# 10_i2c.net
KiCad netlist of a schematic drawn in Altium Designer
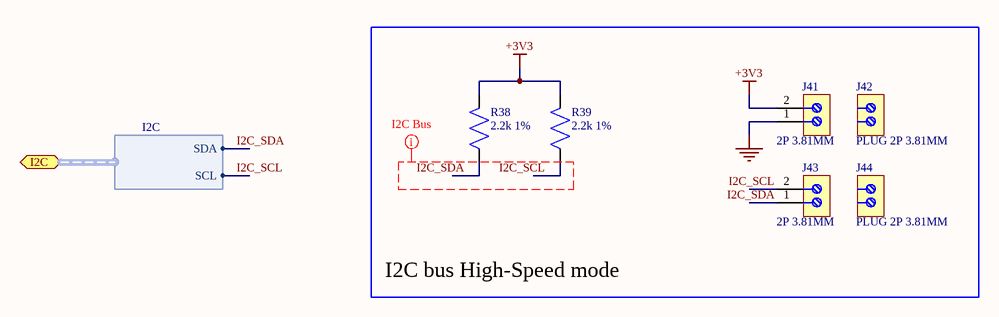
[diagram p0: 10_i2c.SchDoc]

(export (version "E")
  (design (tool "Eeschema 10.0.6"))
  (components
    (comp (ref "J41")
      (value "2P 3.81MM")
      (footprint "TB-2P-3.81MM")
      (description "Terminal Block 2 Positions 3.81MM")
      (libsource (lib "nombre_por_definir") (part "TBLOCK-2P-3.81MM"))
    )
    (comp (ref "J42")
      (value "PLUG 2P 3.81MM")
      (footprint "TB-PLUG-2P-3.81MM")
      (description "Terminal block plug 2positions 3.81mm")
      (libsource (lib "nombre_por_definir") (part "PLUG-2P-3.81MM"))
    )
    (comp (ref "J43")
      (value "2P 3.81MM")
      (footprint "TB-2P-3.81MM")
      (description "Terminal Block 2 Positions 3.81MM")
      (libsource (lib "nombre_por_definir") (part "TBLOCK-2P-3.81MM"))
    )
    (comp (ref "J44")
      (value "PLUG 2P 3.81MM")
      (footprint "TB-PLUG-2P-3.81MM")
      (description "Terminal block plug 2positions 3.81mm")
      (libsource (lib "nombre_por_definir") (part "PLUG-2P-3.81MM"))
    )
    (comp (ref "R38")
      (value "2.2k 1%")
      (footprint "R0603")
      (description "±1% 2.2kΩ ±100ppm/℃ 0.1W 0603 Chip Resistor - Surface Mount")
      (fields (field (name "LCSC PART") "C4190"))
      (libsource (lib "nombre_por_definir") (part "0603WAF2201T5E"))
    )
    (comp (ref "R39")
      (value "2.2k 1%")
      (footprint "R0603")
      (description "±1% 2.2kΩ ±100ppm/℃ 0.1W 0603 Chip Resistor - Surface Mount")
      (fields (field (name "LCSC PART") "C4190"))
      (libsource (lib "nombre_por_definir") (part "0603WAF2201T5E"))
    )
  )
  (nets
    (net (code "2") (name "+3V3") (class "Default")
      (node (ref "J41") (pin "2") (pinfunction "2_2") (pintype "passive"))
      (node (ref "R38") (pin "2") (pinfunction "2_2") (pintype "passive"))
      (node (ref "R39") (pin "2") (pinfunction "2_2") (pintype "passive"))
    )
    (net (code "3") (name "/I2C_SCL") (class "Default")
      (node (ref "J43") (pin "2") (pinfunction "2_2") (pintype "passive"))
      (node (ref "R39") (pin "1") (pinfunction "1_1") (pintype "passive"))
    )
    (net (code "4") (name "/I2C_SDA") (class "Default")
      (node (ref "J43") (pin "1") (pinfunction "1_1") (pintype "passive"))
      (node (ref "R38") (pin "1") (pinfunction "1_1") (pintype "passive"))
    )
    (net (code "6") (name "GND") (class "Default")
      (node (ref "J41") (pin "1") (pinfunction "1_1") (pintype "passive"))
    )
  )
)
